# Solar_Breakout.net
KiCad netlist of a schematic drawn in EAGLE
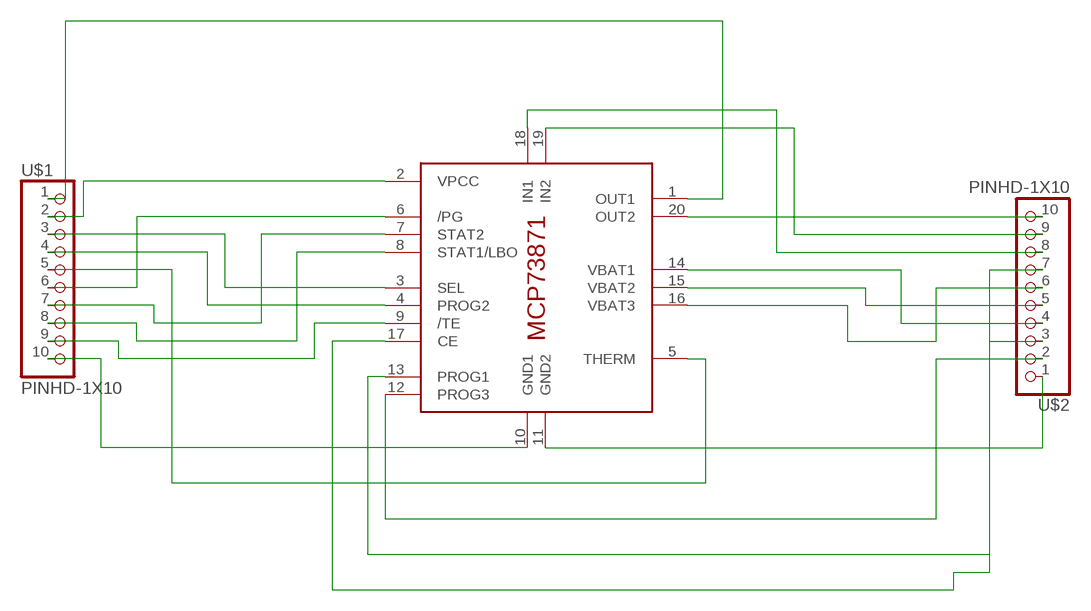
[diagram p0: schematic, sheet 1]

(export (version "E")
  (design (tool "Eeschema 10.0.6"))
  (components
    (comp (ref "IC1")
      (value "MCP73871")
      (footprint "eagle-import:QFN20")
      (libsource (lib "eagle-import") (part "MCP73871"))
    )
    (comp (ref "U$1")
      (value "PINHD-1X10")
      (footprint "eagle-import:1X10-BIG")
      (libsource (lib "eagle-import") (part "PINHD-1X10"))
    )
    (comp (ref "U$2")
      (value "PINHD-1X10")
      (footprint "eagle-import:1X10-BIG")
      (libsource (lib "eagle-import") (part "PINHD-1X10"))
    )
  )
  (nets
    (net (code "1") (name "Net-(IC1-CE)") (class "Default")
      (node (ref "IC1") (pin "17") (pinfunction "CE_17") (pintype "input"))
      (node (ref "U$2") (pin "7") (pinfunction "7_7") (pintype "passive"))
    )
    (net (code "2") (name "Net-(IC1-GND1)") (class "Default")
      (node (ref "IC1") (pin "10") (pinfunction "GND1_10") (pintype "power_in"))
      (node (ref "U$1") (pin "10") (pinfunction "10_10") (pintype "passive"))
    )
    (net (code "3") (name "Net-(IC1-GND2)") (class "Default")
      (node (ref "IC1") (pin "11") (pinfunction "GND2_11") (pintype "power_in"))
      (node (ref "U$2") (pin "1") (pinfunction "1_1") (pintype "passive"))
    )
    (net (code "4") (name "Net-(IC1-IN1)") (class "Default")
      (node (ref "IC1") (pin "18") (pinfunction "IN1_18") (pintype "input"))
      (node (ref "U$2") (pin "8") (pinfunction "8_8") (pintype "passive"))
    )
    (net (code "5") (name "Net-(IC1-IN2)") (class "Default")
      (node (ref "IC1") (pin "19") (pinfunction "IN2_19") (pintype "input"))
      (node (ref "U$2") (pin "9") (pinfunction "9_9") (pintype "passive"))
    )
    (net (code "6") (name "Net-(IC1-OUT1)") (class "Default")
      (node (ref "IC1") (pin "1") (pinfunction "OUT1_1") (pintype "output"))
      (node (ref "U$1") (pin "1") (pinfunction "1_1") (pintype "passive"))
    )
    (net (code "7") (name "Net-(IC1-OUT2)") (class "Default")
      (node (ref "IC1") (pin "20") (pinfunction "OUT2_20") (pintype "output"))
      (node (ref "U$2") (pin "10") (pinfunction "10_10") (pintype "passive"))
    )
    (net (code "8") (name "Net-(IC1-PROG1)") (class "Default")
      (node (ref "IC1") (pin "13") (pinfunction "PROG1_13") (pintype "input"))
      (node (ref "U$2") (pin "3") (pinfunction "3_3") (pintype "passive"))
    )
    (net (code "9") (name "Net-(IC1-PROG2)") (class "Default")
      (node (ref "IC1") (pin "4") (pinfunction "PROG2_4") (pintype "input"))
      (node (ref "U$1") (pin "4") (pinfunction "4_4") (pintype "passive"))
    )
    (net (code "10") (name "Net-(IC1-PROG3)") (class "Default")
      (node (ref "IC1") (pin "12") (pinfunction "PROG3_12") (pintype "input"))
      (node (ref "U$2") (pin "2") (pinfunction "2_2") (pintype "passive"))
    )
    (net (code "11") (name "Net-(IC1-SEL)") (class "Default")
      (node (ref "IC1") (pin "3") (pinfunction "SEL_3") (pintype "input"))
      (node (ref "U$1") (pin "3") (pinfunction "3_3") (pintype "passive"))
    )
    (net (code "12") (name "Net-(IC1-STAT1{slash}LBO)") (class "Default")
      (node (ref "IC1") (pin "8") (pinfunction "STAT1/LBO_8") (pintype "output"))
      (node (ref "U$1") (pin "8") (pinfunction "8_8") (pintype "passive"))
    )
    (net (code "13") (name "Net-(IC1-STAT2)") (class "Default")
      (node (ref "IC1") (pin "7") (pinfunction "STAT2_7") (pintype "output"))
      (node (ref "U$1") (pin "7") (pinfunction "7_7") (pintype "passive"))
    )
    (net (code "14") (name "Net-(IC1-THERM)") (class "Default")
      (node (ref "IC1") (pin "5") (pinfunction "THERM_5") (pintype "input"))
      (node (ref "U$1") (pin "5") (pinfunction "5_5") (pintype "passive"))
    )
    (net (code "15") (name "Net-(IC1-VBAT1)") (class "Default")
      (node (ref "IC1") (pin "14") (pinfunction "VBAT1_14") (pintype "output"))
      (node (ref "U$2") (pin "4") (pinfunction "4_4") (pintype "passive"))
    )
    (net (code "16") (name "Net-(IC1-VBAT2)") (class "Default")
      (node (ref "IC1") (pin "15") (pinfunction "VBAT2_15") (pintype "output"))
      (node (ref "U$2") (pin "5") (pinfunction "5_5") (pintype "passive"))
    )
    (net (code "17") (name "Net-(IC1-VBAT3)") (class "Default")
      (node (ref "IC1") (pin "16") (pinfunction "VBAT3_16") (pintype "output"))
      (node (ref "U$2") (pin "6") (pinfunction "6_6") (pintype "passive"))
    )
    (net (code "18") (name "Net-(IC1-VPCC)") (class "Default")
      (node (ref "IC1") (pin "2") (pinfunction "VPCC_2") (pintype "input"))
      (node (ref "U$1") (pin "2") (pinfunction "2_2") (pintype "passive"))
    )
    (net (code "19") (name "Net-(IC1-{slash}PG)") (class "Default")
      (node (ref "IC1") (pin "6") (pinfunction "/PG_6") (pintype "output"))
      (node (ref "U$1") (pin "6") (pinfunction "6_6") (pintype "passive"))
    )
    (net (code "20") (name "Net-(IC1-{slash}TE)") (class "Default")
      (node (ref "IC1") (pin "9") (pinfunction "/TE_9") (pintype "input"))
      (node (ref "U$1") (pin "9") (pinfunction "9_9") (pintype "passive"))
    )
  )
)
